# Cockpit.net
KiCad netlist of a schematic drawn in Altium Designer
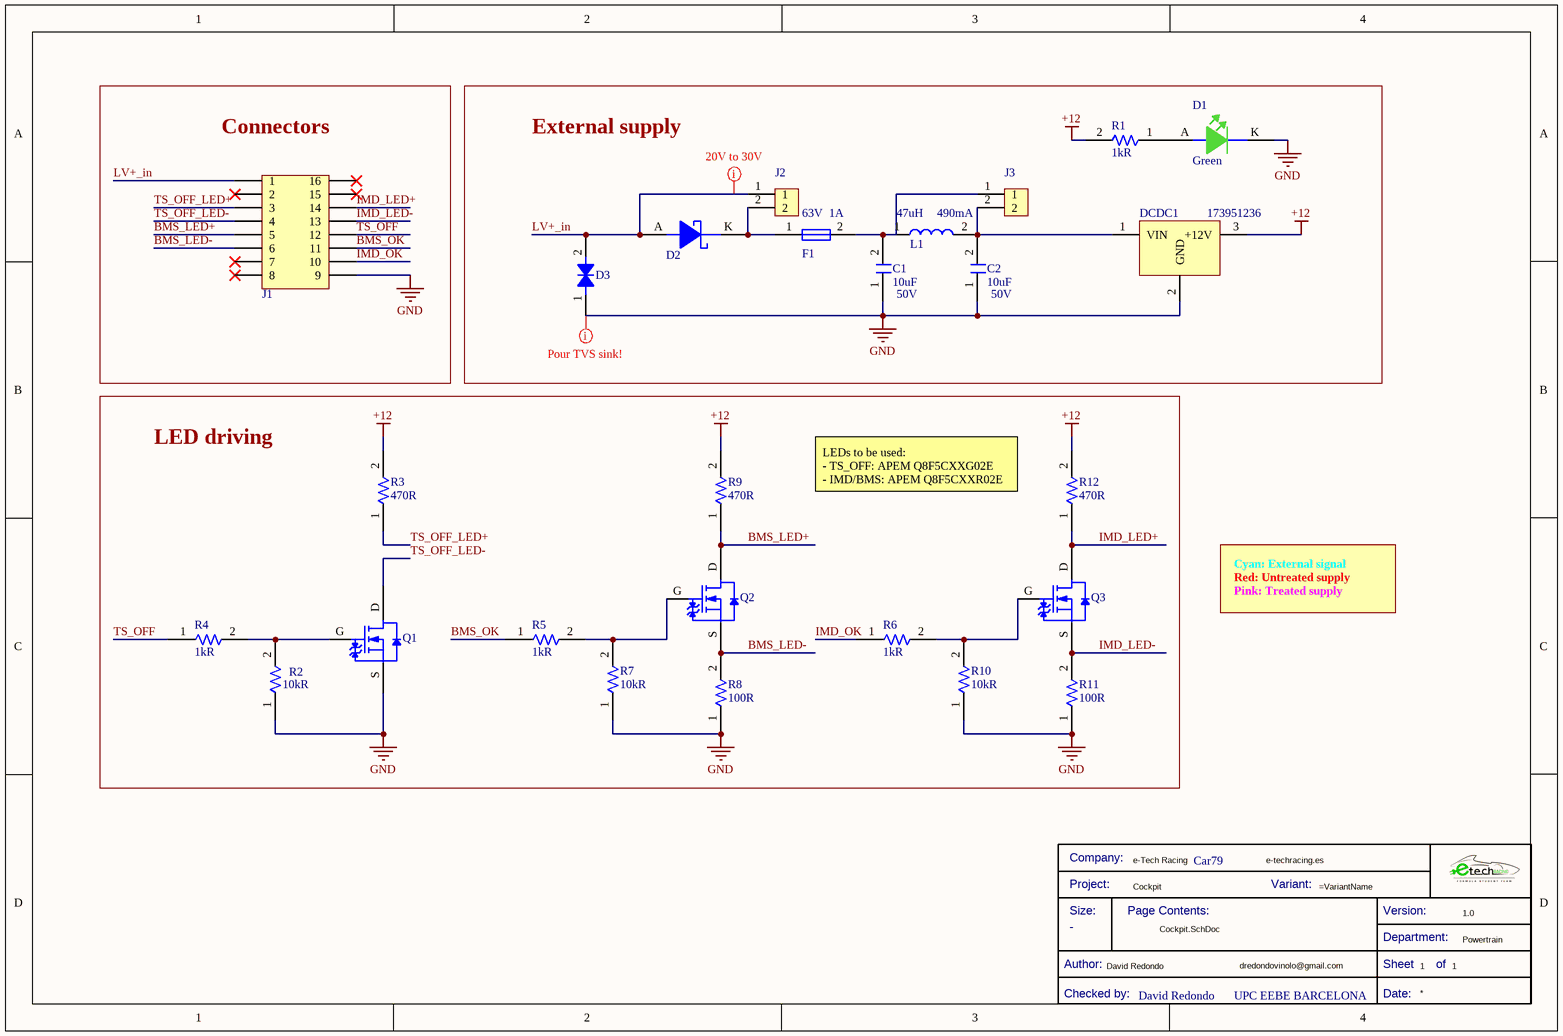
[diagram p0: Cockpit.SchDoc]

(export (version "E")
  (design (tool "Eeschema 10.0.6"))
  (components
    (comp (ref "*")
      (value "Title Block_template")
      (description "Standard Title Block")
      (fields
        (field (name "SIZE") "-")
        (field (name ".CREATOR") "GP")
        (field (name ".PCBCHECK") "GP")
        (field (name ".SCHCHECK") "GP")
      )
      (libsource (lib "e-Tech_Racing") (part "Title Block_template"))
    )
    (comp (ref "C1")
      (value "GRJ32ER71H106KE11L")
      (footprint "C10u-50V-1210FNPMLCC-X7R")
      (description "Multilayer Ceramic Capacitors MLCC - SMD/SMT 1210 10uF 50volts X7R +/-10% Soft Term")
      (fields
        (field (name "MANUFACTURER") "Murata")
        (field (name "VOLTAGE RATING") "50V")
        (field (name "TOLERANCE") "10%")
        (field (name "CAPACITANCE") "10uF")
        (field (name ".CREATOR") "DR")
      )
      (libsource (lib "Passives") (part "C10u-50V-1210FNPMLCC-X7R"))
    )
    (comp (ref "C2")
      (value "GRJ32ER71H106KE11L")
      (footprint "C10u-50V-1210FNPMLCC-X7R")
      (description "Multilayer Ceramic Capacitors MLCC - SMD/SMT 1210 10uF 50volts X7R +/-10% Soft Term")
      (fields
        (field (name "MANUFACTURER") "Murata")
        (field (name "VOLTAGE RATING") "50V")
        (field (name "TOLERANCE") "10%")
        (field (name "CAPACITANCE") "10uF")
        (field (name ".CREATOR") "DR")
      )
      (libsource (lib "Passives") (part "C10u-50V-1210FNPMLCC-X7R"))
    )
    (comp (ref "D1")
      (value "150080VS75000")
      (footprint "LED_0805_WE")
      (description "Led, Green, 570 Nm, 2 V, 30 Ma, 40 Mcd Rohs Compliant: Yes")
      (fields (field (name "COLOR") "Green") (field (name ".CREATOR") "DR"))
      (libsource (lib "Semiconductor") (part "LEDVS-0805-40"))
    )
    (comp (ref "D2")
      (value "MBR0530")
      (footprint "DSC-SOD123")
      (description "VR=30V IF=500mA 30pF P=410mW")
      (fields (field (name ".CREATOR") "GP"))
      (libsource (lib "Filter components") (part "DSC-0.5/30-SOD123"))
    )
    (comp (ref "D3")
      (value "824551301")
      (footprint "DTVS-DO-214AB")
      (description "TVS diode [Würth Elektronik] 824551301 TVS diode")
      (fields (field (name "MANUFACTURER") "Wurth Electronics") (field (name ".CREATOR") "DO"))
      (libsource (lib "Filter components") (part "DTVS-40V-DO-214AB"))
    )
    (comp (ref "DCDC1")
      (value "173951236")
      (footprint "DCDC_Magi3c")
      (description "Fdsm Fixed Step Down Regulator M")
      (libsource (lib "Semiconductor") (part "DCDC-36V/12V-0.5A"))
    )
    (comp (ref "F1")
      (value "0437001.WRA")
      (footprint "Fuse_1206")
      (description "Fuse Chip Fast Acting 1A 63V SMD Solder Pad 1206 Ceramic T/R Automotive")
      (fields
        (field (name "MANUFACTURER") "Littelfuse")
        (field (name "CURRENT RATING") "1A")
        (field (name "VOLTAGE RATING (DC)") "63V")
        (field (name ".CREATOR") "DO")
      )
      (libsource (lib "Filter components") (part "Fuse_1A_63V_1206"))
    )
    (comp (ref "J1")
      (value "1053141116")
      (footprint "J_NanoFit_2x8")
      (description "Nano-Fit Right Angle Header Through Hole 2.50mm Pitch Dual Row 16 Circuits Tin (Sn) Plating Black")
      (fields
        (field (name "MANUFACTURER") "Molex")
        (field (name "MANUFACTURER PART NUMBER") "105314-1116")
        (field (name ".CREATOR") "DO")
      )
      (libsource (lib "Electromechanical") (part "J_NanoFit_2x8"))
    )
    (comp (ref "J2")
      (value "61300211121")
      (footprint "J_Pinheader_1x2")
      (description "CONN HEADER 2 POS 2.54")
      (fields (field (name "MANUFACTURER") "Molex") (field (name ".CREATOR") "GP"))
      (libsource (lib "Electromechanical") (part "J_Jumper"))
    )
    (comp (ref "J3")
      (value "61300211121")
      (footprint "J_Pinheader_1x2")
      (description "CONN HEADER 2 POS 2.54")
      (fields (field (name "MANUFACTURER") "Molex") (field (name ".CREATOR") "GP"))
      (libsource (lib "Electromechanical") (part "J_Jumper"))
    )
    (comp (ref "L1")
      (value "CDC5D23BNP-470KC")
      (footprint "L_47u-490mA_CF")
      (description "Inductor Power Unshielded Wirewound 47uH 10% 100KHz Ferrite 490mA 546mOhm DCR T/R")
      (fields
        (field (name "MANUFACTURER") "Sumida")
        (field (name "TOLERANCE") "10%")
        (field (name "CURRENT RATING") "490mA")
        (field (name "INDUCTANCE") "47uH")
        (field (name ".CREATOR") "GP")
      )
      (libsource (lib "Passives") (part "L_47u-490mA_CF"))
    )
    (comp (ref "Q1")
      (value "CPH3455-TL-H")
      (footprint "TRT-NCH-3/35-CPH")
      (description "CPH3455-TL-H N-channel MOSFET Transistor; 3 A; 35 V; 3-Pin CPH")
      (fields (field (name "MANUFACTURER") "ON Semiconductor") (field (name ".CREATOR") "GP"))
      (libsource (lib "Semiconductor") (part "TRT-NCH-3/35-CPH"))
    )
    (comp (ref "Q2")
      (value "CPH3455-TL-H")
      (footprint "TRT-NCH-3/35-CPH")
      (description "CPH3455-TL-H N-channel MOSFET Transistor; 3 A; 35 V; 3-Pin CPH")
      (fields (field (name "MANUFACTURER") "ON Semiconductor") (field (name ".CREATOR") "GP"))
      (libsource (lib "Semiconductor") (part "TRT-NCH-3/35-CPH"))
    )
    (comp (ref "Q3")
      (value "CPH3455-TL-H")
      (footprint "TRT-NCH-3/35-CPH")
      (description "CPH3455-TL-H N-channel MOSFET Transistor; 3 A; 35 V; 3-Pin CPH")
      (fields (field (name "MANUFACTURER") "ON Semiconductor") (field (name ".CREATOR") "GP"))
      (libsource (lib "Semiconductor") (part "TRT-NCH-3/35-CPH"))
    )
    (comp (ref "R1")
      (value "CR0805-JW-102ELF")
      (footprint "R0805FTK")
      (description "Res Thick Film 0805 1K Ohm 5% 1/8W ±200ppm/°C Molded SMD SMD Paper Tape on Plastic Reel")
      (fields
        (field (name "TOLERANCE") "5%")
        (field (name "RESISTANCE") "1kR")
        (field (name ".CREATOR") "GP")
      )
      (libsource (lib "Passives") (part "R1k-0805FTK"))
    )
    (comp (ref "R2")
      (value "CR0805-JW-103ELF")
      (footprint "R0805FTK")
      (fields
        (field (name "TOLERANCE") "5%")
        (field (name "RESISTANCE") "10kR")
        (field (name ".CREATOR") "DR")
      )
      (libsource (lib "Passives") (part "R10k-0805FTK"))
    )
    (comp (ref "R3")
      (value "CR0805-FX-4700GLF")
      (footprint "R0805FTK")
      (description "Res Thick Film 0805 470 Ohm 1% 1/8W ±100ppm/°C Molded SMD SMD Paper Tape on Plastic Reel")
      (fields
        (field (name "TOLERANCE") "1%")
        (field (name "RESISTANCE") "470R")
        (field (name ".CREATOR") "DR")
      )
      (libsource (lib "Passives") (part "R470-0805FTK"))
    )
    (comp (ref "R4")
      (value "CR0805-JW-102ELF")
      (footprint "R0805FTK")
      (description "Res Thick Film 0805 1K Ohm 5% 1/8W ±200ppm/°C Molded SMD SMD Paper Tape on Plastic Reel")
      (fields
        (field (name "TOLERANCE") "5%")
        (field (name "RESISTANCE") "1kR")
        (field (name ".CREATOR") "GP")
      )
      (libsource (lib "Passives") (part "R1k-0805FTK"))
    )
    (comp (ref "R5")
      (value "CR0805-JW-102ELF")
      (footprint "R0805FTK")
      (description "Res Thick Film 0805 1K Ohm 5% 1/8W ±200ppm/°C Molded SMD SMD Paper Tape on Plastic Reel")
      (fields
        (field (name "TOLERANCE") "5%")
        (field (name "RESISTANCE") "1kR")
        (field (name ".CREATOR") "GP")
      )
      (libsource (lib "Passives") (part "R1k-0805FTK"))
    )
    (comp (ref "R6")
      (value "CR0805-JW-102ELF")
      (footprint "R0805FTK")
      (description "Res Thick Film 0805 1K Ohm 5% 1/8W ±200ppm/°C Molded SMD SMD Paper Tape on Plastic Reel")
      (fields
        (field (name "TOLERANCE") "5%")
        (field (name "RESISTANCE") "1kR")
        (field (name ".CREATOR") "GP")
      )
      (libsource (lib "Passives") (part "R1k-0805FTK"))
    )
    (comp (ref "R7")
      (value "CR0805-JW-103ELF")
      (footprint "R0805FTK")
      (fields
        (field (name "TOLERANCE") "5%")
        (field (name "RESISTANCE") "10kR")
        (field (name ".CREATOR") "DR")
      )
      (libsource (lib "Passives") (part "R10k-0805FTK"))
    )
    (comp (ref "R8")
      (value "CR0805-FX-1000ELF")
      (footprint "R0805FTK")
      (description "Res Thick Film 0805 100 Ohm 1% 1/8W ±100ppm/°C Molded SMD SMD Paper Tape on Plastic Reel")
      (fields
        (field (name "TOLERANCE") "1%")
        (field (name "RESISTANCE") "100R")
        (field (name ".CREATOR") "DR")
      )
      (libsource (lib "Passives") (part "R100-0805FTK"))
    )
    (comp (ref "R9")
      (value "CR0805-FX-4700GLF")
      (footprint "R0805FTK")
      (description "Res Thick Film 0805 470 Ohm 1% 1/8W ±100ppm/°C Molded SMD SMD Paper Tape on Plastic Reel")
      (fields
        (field (name "TOLERANCE") "1%")
        (field (name "RESISTANCE") "470R")
        (field (name ".CREATOR") "DR")
      )
      (libsource (lib "Passives") (part "R470-0805FTK"))
    )
    (comp (ref "R10")
      (value "CR0805-JW-103ELF")
      (footprint "R0805FTK")
      (fields
        (field (name "TOLERANCE") "5%")
        (field (name "RESISTANCE") "10kR")
        (field (name ".CREATOR") "DR")
      )
      (libsource (lib "Passives") (part "R10k-0805FTK"))
    )
    (comp (ref "R11")
      (value "CR0805-FX-1000ELF")
      (footprint "R0805FTK")
      (description "Res Thick Film 0805 100 Ohm 1% 1/8W ±100ppm/°C Molded SMD SMD Paper Tape on Plastic Reel")
      (fields
        (field (name "TOLERANCE") "1%")
        (field (name "RESISTANCE") "100R")
        (field (name ".CREATOR") "DR")
      )
      (libsource (lib "Passives") (part "R100-0805FTK"))
    )
    (comp (ref "R12")
      (value "CR0805-FX-4700GLF")
      (footprint "R0805FTK")
      (description "Res Thick Film 0805 470 Ohm 1% 1/8W ±100ppm/°C Molded SMD SMD Paper Tape on Plastic Reel")
      (fields
        (field (name "TOLERANCE") "1%")
        (field (name "RESISTANCE") "470R")
        (field (name ".CREATOR") "DR")
      )
      (libsource (lib "Passives") (part "R470-0805FTK"))
    )
  )
  (nets
    (net (code "1") (name "+12") (class "Default")
      (node (ref "DCDC1") (pin "3") (pinfunction "+12V_3") (pintype "passive"))
      (node (ref "R1") (pin "2") (pinfunction "2_2") (pintype "passive"))
      (node (ref "R12") (pin "2") (pinfunction "2_2") (pintype "passive"))
      (node (ref "R3") (pin "2") (pinfunction "2_2") (pintype "passive"))
      (node (ref "R9") (pin "2") (pinfunction "2_2") (pintype "passive"))
    )
    (net (code "2") (name "/BMS_LED+") (class "Default")
      (node (ref "J1") (pin "5") (pinfunction "5_5") (pintype "passive"))
      (node (ref "Q2") (pin "D") (pinfunction "D_D") (pintype "passive"))
      (node (ref "R9") (pin "1") (pinfunction "1_1") (pintype "passive"))
    )
    (net (code "3") (name "/BMS_LED-") (class "Default")
      (node (ref "J1") (pin "6") (pinfunction "6_6") (pintype "passive"))
      (node (ref "Q2") (pin "S") (pinfunction "S_S") (pintype "passive"))
      (node (ref "R8") (pin "2") (pinfunction "2_2") (pintype "passive"))
    )
    (net (code "4") (name "/BMS_OK") (class "Default")
      (node (ref "J1") (pin "11") (pinfunction "11_11") (pintype "passive"))
      (node (ref "R5") (pin "1") (pinfunction "1_1") (pintype "passive"))
    )
    (net (code "5") (name "/IMD_LED+") (class "Default")
      (node (ref "J1") (pin "14") (pinfunction "14_14") (pintype "passive"))
      (node (ref "Q3") (pin "D") (pinfunction "D_D") (pintype "passive"))
      (node (ref "R12") (pin "1") (pinfunction "1_1") (pintype "passive"))
    )
    (net (code "6") (name "/IMD_LED-") (class "Default")
      (node (ref "J1") (pin "13") (pinfunction "13_13") (pintype "passive"))
      (node (ref "Q3") (pin "S") (pinfunction "S_S") (pintype "passive"))
      (node (ref "R11") (pin "2") (pinfunction "2_2") (pintype "passive"))
    )
    (net (code "7") (name "/IMD_OK") (class "Default")
      (node (ref "J1") (pin "10") (pinfunction "10_10") (pintype "passive"))
      (node (ref "R6") (pin "1") (pinfunction "1_1") (pintype "passive"))
    )
    (net (code "8") (name "/LV+_in") (class "Default")
      (node (ref "D2") (pin "A") (pinfunction "A_A") (pintype "passive"))
      (node (ref "D3") (pin "2") (pinfunction "2_2") (pintype "passive"))
      (node (ref "J1") (pin "1") (pinfunction "1_1") (pintype "passive"))
      (node (ref "J2") (pin "1") (pinfunction "1_1") (pintype "passive"))
    )
    (net (code "9") (name "/TS_OFF") (class "Default")
      (node (ref "J1") (pin "12") (pinfunction "12_12") (pintype "passive"))
      (node (ref "R4") (pin "1") (pinfunction "1_1") (pintype "passive"))
    )
    (net (code "10") (name "/TS_OFF_LED+") (class "Default")
      (node (ref "J1") (pin "3") (pinfunction "3_3") (pintype "passive"))
      (node (ref "R3") (pin "1") (pinfunction "1_1") (pintype "passive"))
    )
    (net (code "11") (name "/TS_OFF_LED-") (class "Default")
      (node (ref "J1") (pin "4") (pinfunction "4_4") (pintype "passive"))
      (node (ref "Q1") (pin "D") (pinfunction "D_D") (pintype "passive"))
    )
    (net (code "12") (name "GND") (class "Default")
      (node (ref "C1") (pin "1") (pinfunction "1_1") (pintype "passive"))
      (node (ref "C2") (pin "1") (pinfunction "1_1") (pintype "passive"))
      (node (ref "D1") (pin "K") (pinfunction "K_K") (pintype "passive"))
      (node (ref "D3") (pin "1") (pinfunction "1_1") (pintype "passive"))
      (node (ref "DCDC1") (pin "2") (pinfunction "GND_2") (pintype "passive"))
      (node (ref "J1") (pin "9") (pinfunction "9_9") (pintype "passive"))
      (node (ref "Q1") (pin "S") (pinfunction "S_S") (pintype "passive"))
      (node (ref "R10") (pin "1") (pinfunction "1_1") (pintype "passive"))
      (node (ref "R11") (pin "1") (pinfunction "1_1") (pintype "passive"))
      (node (ref "R2") (pin "1") (pinfunction "1_1") (pintype "passive"))
      (node (ref "R7") (pin "1") (pinfunction "1_1") (pintype "passive"))
      (node (ref "R8") (pin "1") (pinfunction "1_1") (pintype "passive"))
    )
    (net (code "13") (name "Net-(C1-Pad2)") (class "Default")
      (node (ref "C1") (pin "2") (pinfunction "2_2") (pintype "passive"))
      (node (ref "F1") (pin "2") (pinfunction "2_2") (pintype "passive"))
      (node (ref "J3") (pin "1") (pinfunction "1_1") (pintype "passive"))
      (node (ref "L1") (pin "1") (pinfunction "1_1") (pintype "passive"))
    )
    (net (code "14") (name "Net-(D1-PadA)") (class "Default")
      (node (ref "D1") (pin "A") (pinfunction "A_A") (pintype "passive"))
      (node (ref "R1") (pin "1") (pinfunction "1_1") (pintype "passive"))
    )
    (net (code "15") (name "Net-(D2-PadK)") (class "Default")
      (node (ref "D2") (pin "K") (pinfunction "K_K") (pintype "passive"))
      (node (ref "F1") (pin "1") (pinfunction "1_1") (pintype "passive"))
      (node (ref "J2") (pin "2") (pinfunction "2_2") (pintype "passive"))
    )
    (net (code "16") (name "Net-(DCDC1-VIN)") (class "Default")
      (node (ref "C2") (pin "2") (pinfunction "2_2") (pintype "passive"))
      (node (ref "DCDC1") (pin "1") (pinfunction "VIN_1") (pintype "passive"))
      (node (ref "J3") (pin "2") (pinfunction "2_2") (pintype "passive"))
      (node (ref "L1") (pin "2") (pinfunction "2_2") (pintype "passive"))
    )
    (net (code "17") (name "Net-(Q1-PadG)") (class "Default")
      (node (ref "Q1") (pin "G") (pinfunction "G_G") (pintype "passive"))
      (node (ref "R2") (pin "2") (pinfunction "2_2") (pintype "passive"))
      (node (ref "R4") (pin "2") (pinfunction "2_2") (pintype "passive"))
    )
    (net (code "18") (name "Net-(Q2-PadG)") (class "Default")
      (node (ref "Q2") (pin "G") (pinfunction "G_G") (pintype "passive"))
      (node (ref "R5") (pin "2") (pinfunction "2_2") (pintype "passive"))
      (node (ref "R7") (pin "2") (pinfunction "2_2") (pintype "passive"))
    )
    (net (code "19") (name "Net-(Q3-PadG)") (class "Default")
      (node (ref "Q3") (pin "G") (pinfunction "G_G") (pintype "passive"))
      (node (ref "R10") (pin "2") (pinfunction "2_2") (pintype "passive"))
      (node (ref "R6") (pin "2") (pinfunction "2_2") (pintype "passive"))
    )
    (net (code "20") (name "unconnected-(J1-Pad2)") (class "Default")
      (node (ref "J1") (pin "2") (pinfunction "2_2") (pintype "passive+no_connect"))
    )
    (net (code "21") (name "unconnected-(J1-Pad7)") (class "Default")
      (node (ref "J1") (pin "7") (pinfunction "7_7") (pintype "passive+no_connect"))
    )
    (net (code "22") (name "unconnected-(J1-Pad8)") (class "Default")
      (node (ref "J1") (pin "8") (pinfunction "8_8") (pintype "passive+no_connect"))
    )
    (net (code "23") (name "unconnected-(J1-Pad15)") (class "Default")
      (node (ref "J1") (pin "15") (pinfunction "15_15") (pintype "passive+no_connect"))
    )
    (net (code "24") (name "unconnected-(J1-Pad16)") (class "Default")
      (node (ref "J1") (pin "16") (pinfunction "16_16") (pintype "passive+no_connect"))
    )
  )
)
